# SmartWatch_SCH.net
KiCad netlist of a schematic drawn in EAGLE
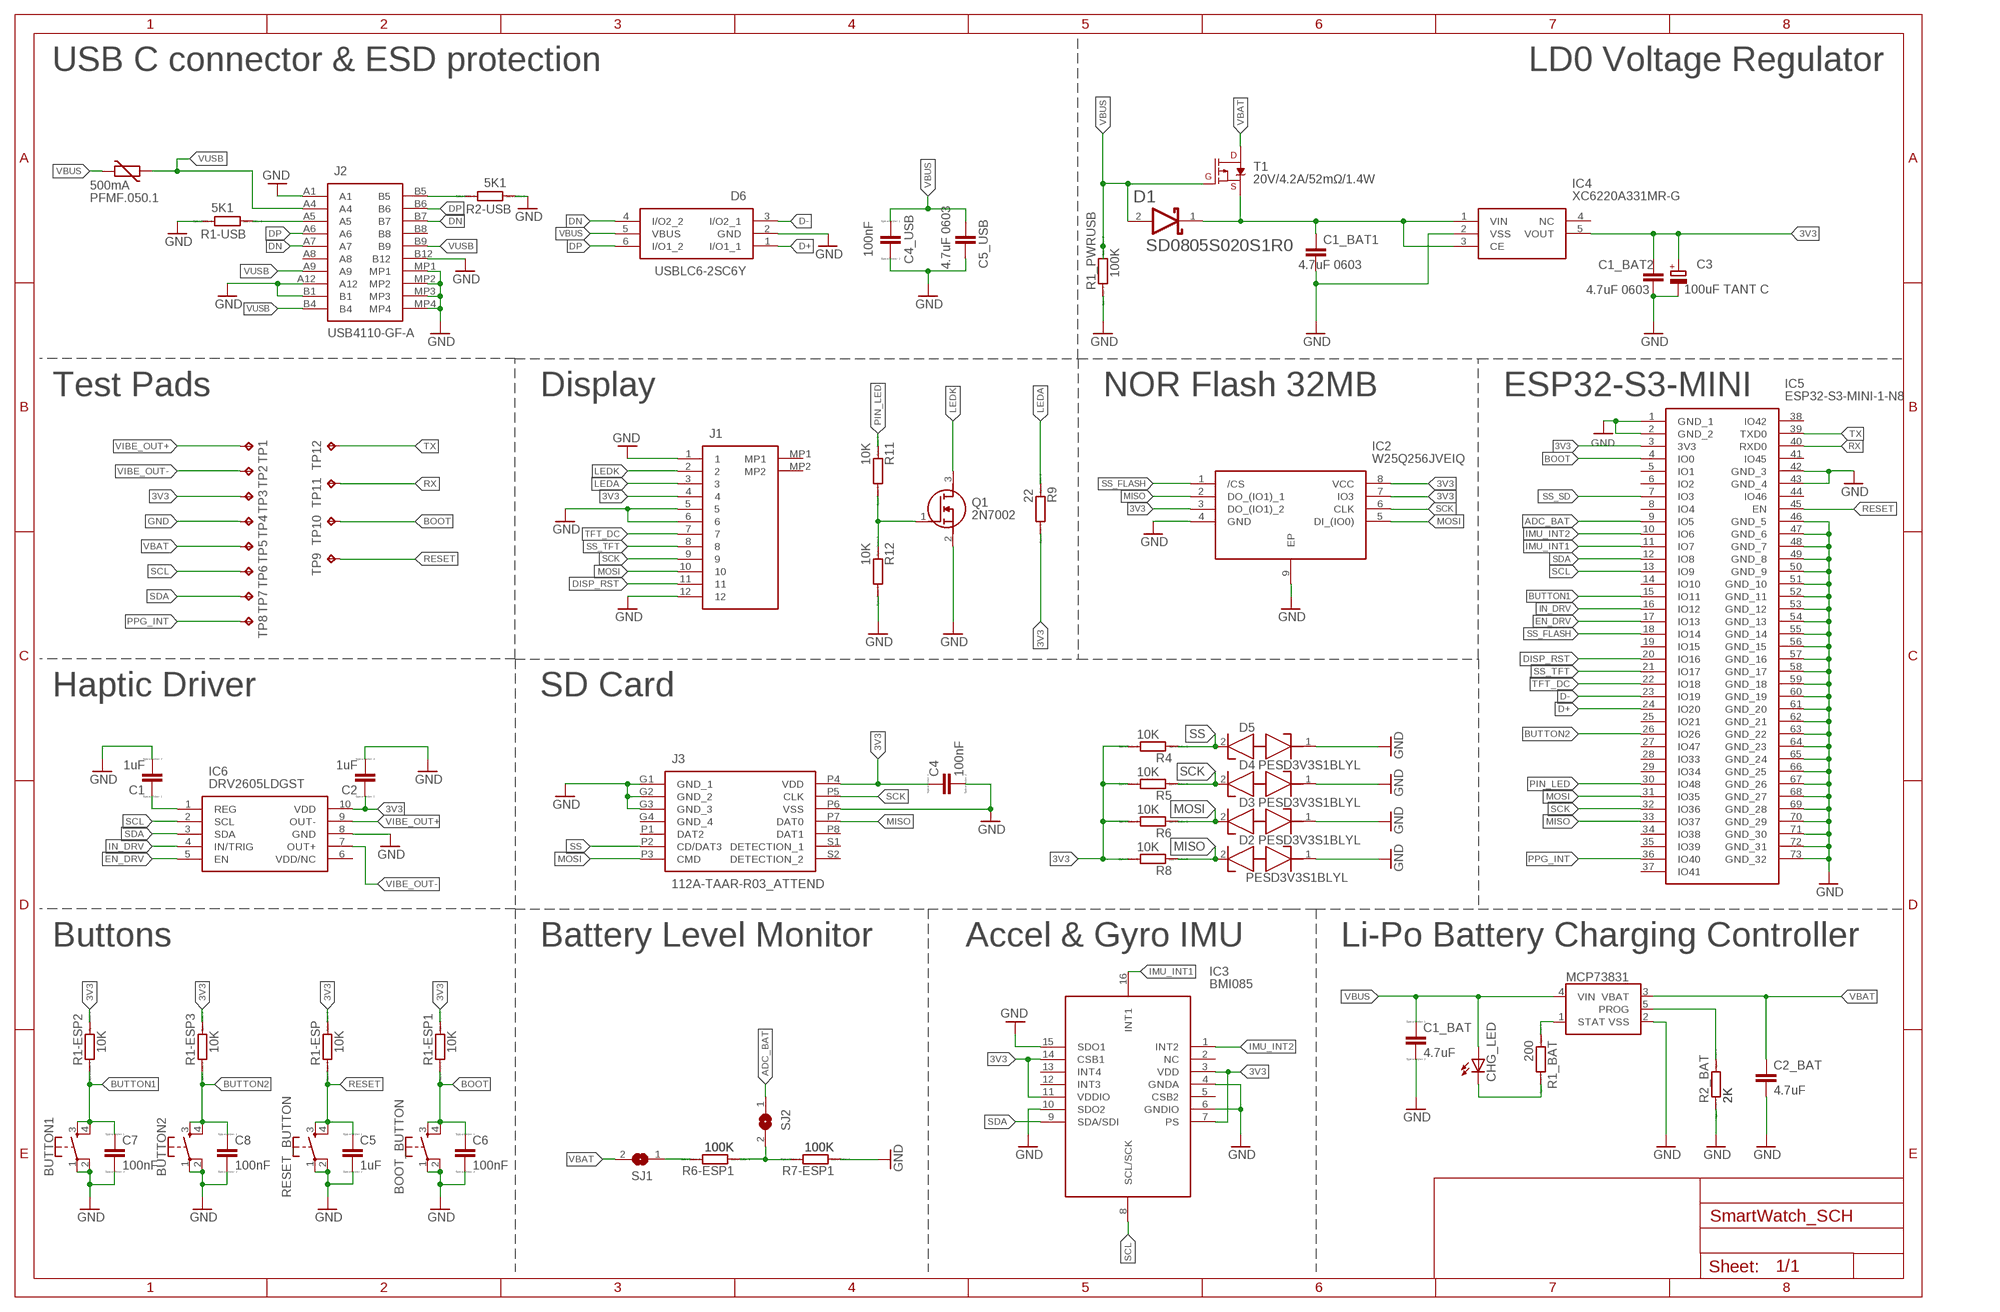
[diagram p0: schematic, sheet 1]

(export (version "E")
  (design (tool "Eeschema 10.0.6"))
  (components
    (comp (ref "BOOT_BUTTON")
      (value "SPARKFUN-SWITCHES_MOMENTARY-SWITCH-SPST-2-SMD-4.6X2.8MM")
      (footprint "eagle-import:SPARKFUN-SWITCHES_TACTILE_SWITCH_SMD_4.6X2.8MM")
      (libsource (lib "eagle-import") (part "SPARKFUN-SWITCHES_MOMENTARY-SWITCH-SPST-2-SMD-4.6X2.8MM"))
    )
    (comp (ref "BUTTON1")
      (value "SPARKFUN-SWITCHES_MOMENTARY-SWITCH-SPST-2-SMD-4.6X2.8MM")
      (footprint "eagle-import:SPARKFUN-SWITCHES_TACTILE_SWITCH_SMD_4.6X2.8MM")
      (libsource (lib "eagle-import") (part "SPARKFUN-SWITCHES_MOMENTARY-SWITCH-SPST-2-SMD-4.6X2.8MM"))
    )
    (comp (ref "BUTTON2")
      (value "SPARKFUN-SWITCHES_MOMENTARY-SWITCH-SPST-2-SMD-4.6X2.8MM")
      (footprint "eagle-import:SPARKFUN-SWITCHES_TACTILE_SWITCH_SMD_4.6X2.8MM")
      (libsource (lib "eagle-import") (part "SPARKFUN-SWITCHES_MOMENTARY-SWITCH-SPST-2-SMD-4.6X2.8MM"))
    )
    (comp (ref "C1")
      (value "1uF")
      (footprint "eagle-import:EAGLE-LTSPICE_C0402")
      (libsource (lib "eagle-import") (part "EAGLE-LTSPICE_CC0402"))
    )
    (comp (ref "C1_BAT")
      (value "4.7uF")
      (footprint "eagle-import:EAGLE-LTSPICE_C0402")
      (libsource (lib "eagle-import") (part "EAGLE-LTSPICE_CC0402"))
    )
    (comp (ref "C1_BAT1")
      (value "4.7uF 0603")
      (footprint "eagle-import:RCL_C0603")
      (libsource (lib "eagle-import") (part "RCL_C-EUC0603"))
    )
    (comp (ref "C1_BAT2")
      (value "4.7uF 0603")
      (footprint "eagle-import:RCL_C0603")
      (libsource (lib "eagle-import") (part "RCL_C-EUC0603"))
    )
    (comp (ref "C2")
      (value "1uF")
      (footprint "eagle-import:EAGLE-LTSPICE_C0402")
      (libsource (lib "eagle-import") (part "EAGLE-LTSPICE_CC0402"))
    )
    (comp (ref "C2_BAT")
      (value "4.7uF")
      (footprint "eagle-import:RCL_C0603")
      (libsource (lib "eagle-import") (part "RCL_C-EUC0603"))
    )
    (comp (ref "C3")
      (value "100uF TANT C")
      (footprint "eagle-import:CT3528")
      (libsource (lib "eagle-import") (part "CPOL-EUCT3528"))
    )
    (comp (ref "C4")
      (value "100nF")
      (footprint "eagle-import:EAGLE-LTSPICE_C0402")
      (libsource (lib "eagle-import") (part "EAGLE-LTSPICE_CC0402"))
    )
    (comp (ref "C4_USB")
      (value "100nF")
      (footprint "eagle-import:EAGLE-LTSPICE_C0402")
      (libsource (lib "eagle-import") (part "EAGLE-LTSPICE_CC0402"))
    )
    (comp (ref "C5")
      (value "1uF")
      (footprint "eagle-import:EAGLE-LTSPICE_C0402")
      (libsource (lib "eagle-import") (part "EAGLE-LTSPICE_CC0402"))
    )
    (comp (ref "C5_USB")
      (value "4.7uF 0603")
      (footprint "eagle-import:RCL_C0603")
      (libsource (lib "eagle-import") (part "RCL_C-EUC0603"))
    )
    (comp (ref "C6")
      (value "100nF")
      (footprint "eagle-import:EAGLE-LTSPICE_C0402")
      (libsource (lib "eagle-import") (part "EAGLE-LTSPICE_CC0402"))
    )
    (comp (ref "C7")
      (value "100nF")
      (footprint "eagle-import:EAGLE-LTSPICE_C0402")
      (libsource (lib "eagle-import") (part "EAGLE-LTSPICE_CC0402"))
    )
    (comp (ref "C8")
      (value "100nF")
      (footprint "eagle-import:EAGLE-LTSPICE_C0402")
      (libsource (lib "eagle-import") (part "EAGLE-LTSPICE_CC0402"))
    )
    (comp (ref "CHG_LED")
      (value "ADAFRUIT_LEDCHIP-LED0603")
      (footprint "eagle-import:ADAFRUIT_CHIP-LED0603")
      (libsource (lib "eagle-import") (part "ADAFRUIT_LEDCHIP-LED0603"))
    )
    (comp (ref "D1")
      (value "AVX---SD0805S020S1R0_AVX_SD0805S020S1R0AVX_SD0805S020S1R0_0_0")
      (footprint "eagle-import:AVX---SD0805S020S1R0_AVX_SD0805S020S1R0_0")
      (fields
        (field (name "DIGIKEY_PART_NUMBER") "478-7800-1-ND")
        (field (name "MF") "AVX")
        (field (name "MOUSER_PART_NUMBER") "581-SD0805S020S1R0")
      )
      (libsource (lib "eagle-import") (part "AVX---SD0805S020S1R0_AVX_SD0805S020S1R0AVX_SD0805S020S1R0_0_0"))
    )
    (comp (ref "D2")
      (value "PESD3V3S1BLYL")
      (footprint "eagle-import:PESD5V0S1BL315")
      (fields (field (name "MOUSER_PART_NUMBER") "771-PESD3V3S1BLYL"))
      (libsource (lib "eagle-import") (part "PESD3V3S1BLYL"))
    )
    (comp (ref "D3")
      (value "PESD3V3S1BLYL")
      (footprint "eagle-import:PESD5V0S1BL315")
      (fields (field (name "MOUSER_PART_NUMBER") "771-PESD3V3S1BLYL"))
      (libsource (lib "eagle-import") (part "PESD3V3S1BLYL"))
    )
    (comp (ref "D4")
      (value "PESD3V3S1BLYL")
      (footprint "eagle-import:PESD5V0S1BL315")
      (fields (field (name "MOUSER_PART_NUMBER") "771-PESD3V3S1BLYL"))
      (libsource (lib "eagle-import") (part "PESD3V3S1BLYL"))
    )
    (comp (ref "D5")
      (value "PESD3V3S1BLYL")
      (footprint "eagle-import:PESD5V0S1BL315")
      (fields (field (name "MOUSER_PART_NUMBER") "771-PESD3V3S1BLYL"))
      (libsource (lib "eagle-import") (part "PESD3V3S1BLYL"))
    )
    (comp (ref "D6")
      (value "USBLC6-2SC6Y")
      (footprint "eagle-import:SOT95P280X145-6N")
      (fields (field (name "MOUSER_PART_NUMBER") "511-USBLC6-2SC6Y"))
      (libsource (lib "eagle-import") (part "USBLC6-2SC6Y"))
    )
    (comp (ref "IC2")
      (value "W25Q256JVEIQ")
      (footprint "eagle-import:SON127P800X600X80-9N")
      (fields (field (name "MOUSER_PART_NUMBER") "454-W25Q256JVEIQ"))
      (libsource (lib "eagle-import") (part "W25Q256JVEIQ"))
    )
    (comp (ref "IC3")
      (value "BMI085")
      (footprint "eagle-import:BMI085")
      (fields (field (name "MOUSER_PART_NUMBER") "262-BMI085"))
      (libsource (lib "eagle-import") (part "BMI085"))
    )
    (comp (ref "IC4")
      (value "XC6220A331MR-G")
      (footprint "eagle-import:SOT95P280X120-5N")
      (fields (field (name "MOUSER_PART_NUMBER") "865-XC6220A331MR-G"))
      (libsource (lib "eagle-import") (part "XC6220A331MR-G"))
    )
    (comp (ref "IC5")
      (value "ESP32-S3-MINI-1-N8")
      (footprint "eagle-import:ESP32S3MINI1N8")
      (fields (field (name "MOUSER_PART_NUMBER") "356-ESP32-S3-MINI1N8"))
      (libsource (lib "eagle-import") (part "ESP32-S3-MINI-1-N8"))
    )
    (comp (ref "IC6")
      (value "DRV2605LDGST")
      (footprint "eagle-import:SOP50P490X110-10N")
      (fields (field (name "MOUSER_PART_NUMBER") "595-DRV2605LDGST"))
      (libsource (lib "eagle-import") (part "DRV2605LDGST"))
    )
    (comp (ref "J1")
      (value "PCA-6-LA-12-HL-3-T_R")
      (footprint "eagle-import:PCA6LA12HL3TR")
      (fields (field (name "MANUFACTURER_PART_NUMBER") "PCA-6-LA-12-HL-3-T/R"))
      (libsource (lib "eagle-import") (part "PCA-6-LA-12-HL-3-T_R"))
    )
    (comp (ref "J2")
      (value "USB4110-GF-A")
      (footprint "eagle-import:USB4110GFA")
      (fields
        (field (name "MANUFACTURER_PART_NUMBER") "USB4110-GF-A")
        (field (name "MOUSER_PART_NUMBER") "640-USB4110-GF-A")
      )
      (libsource (lib "eagle-import") (part "USB4110-GF-A"))
    )
    (comp (ref "J3")
      (value "112A-TAAR-R03_ATTEND")
      (footprint "eagle-import:112ATAARR03ATTEND")
      (fields (field (name "MANUFACTURER_PART_NUMBER") "112A-TAAR-R03 ATTEND"))
      (libsource (lib "eagle-import") (part "112A-TAAR-R03_ATTEND"))
    )
    (comp (ref "MCP73831")
      (value "SPARKFUN-IC-POWER_MCP73831")
      (footprint "eagle-import:SPARKFUN-IC-POWER_SOT23-5")
      (libsource (lib "eagle-import") (part "SPARKFUN-IC-POWER_MCP73831"))
    )
    (comp (ref "PFMF.050.1")
      (value "500mA")
      (footprint "eagle-import:VARISTOR_CT_CN1812")
      (libsource (lib "eagle-import") (part "VARISTOR_VARISTORCN1812"))
    )
    (comp (ref "Q1")
      (value "2N7002")
      (footprint "eagle-import:SOT96P240X120-3N")
      (fields (field (name "MOUSER_PART_NUMBER") "512-2N7002"))
      (libsource (lib "eagle-import") (part "2N7002"))
    )
    (comp (ref "R1-ESP")
      (value "10K")
      (footprint "eagle-import:EAGLE-LTSPICE_R0402")
      (libsource (lib "eagle-import") (part "EAGLE-LTSPICE_RR0402"))
    )
    (comp (ref "R1-ESP1")
      (value "10K")
      (footprint "eagle-import:EAGLE-LTSPICE_R0402")
      (libsource (lib "eagle-import") (part "EAGLE-LTSPICE_RR0402"))
    )
    (comp (ref "R1-ESP2")
      (value "10K")
      (footprint "eagle-import:EAGLE-LTSPICE_R0402")
      (libsource (lib "eagle-import") (part "EAGLE-LTSPICE_RR0402"))
    )
    (comp (ref "R1-ESP3")
      (value "10K")
      (footprint "eagle-import:EAGLE-LTSPICE_R0402")
      (libsource (lib "eagle-import") (part "EAGLE-LTSPICE_RR0402"))
    )
    (comp (ref "R1-USB")
      (value "5K1")
      (footprint "eagle-import:EAGLE-LTSPICE_R0402")
      (libsource (lib "eagle-import") (part "EAGLE-LTSPICE_RR0402"))
    )
    (comp (ref "R1_BAT")
      (value "200")
      (footprint "eagle-import:EAGLE-LTSPICE_R0402")
      (libsource (lib "eagle-import") (part "EAGLE-LTSPICE_RR0402"))
    )
    (comp (ref "R1_PWRUSB")
      (value "100K")
      (footprint "eagle-import:EAGLE-LTSPICE_R0402")
      (libsource (lib "eagle-import") (part "EAGLE-LTSPICE_RR0402"))
    )
    (comp (ref "R2-USB")
      (value "5K1")
      (footprint "eagle-import:EAGLE-LTSPICE_R0402")
      (libsource (lib "eagle-import") (part "EAGLE-LTSPICE_RR0402"))
    )
    (comp (ref "R2_BAT")
      (value "2K")
      (footprint "eagle-import:EAGLE-LTSPICE_R0402")
      (libsource (lib "eagle-import") (part "EAGLE-LTSPICE_RR0402"))
    )
    (comp (ref "R4")
      (value "10K")
      (footprint "eagle-import:EAGLE-LTSPICE_R0402")
      (libsource (lib "eagle-import") (part "EAGLE-LTSPICE_RR0402"))
    )
    (comp (ref "R5")
      (value "10K")
      (footprint "eagle-import:EAGLE-LTSPICE_R0402")
      (libsource (lib "eagle-import") (part "EAGLE-LTSPICE_RR0402"))
    )
    (comp (ref "R6")
      (value "10K")
      (footprint "eagle-import:EAGLE-LTSPICE_R0402")
      (libsource (lib "eagle-import") (part "EAGLE-LTSPICE_RR0402"))
    )
    (comp (ref "R6-ESP1")
      (value "100K")
      (footprint "eagle-import:EAGLE-LTSPICE_R0402")
      (libsource (lib "eagle-import") (part "EAGLE-LTSPICE_RR0402"))
    )
    (comp (ref "R7-ESP1")
      (value "100K")
      (footprint "eagle-import:EAGLE-LTSPICE_R0402")
      (libsource (lib "eagle-import") (part "EAGLE-LTSPICE_RR0402"))
    )
    (comp (ref "R8")
      (value "10K")
      (footprint "eagle-import:EAGLE-LTSPICE_R0402")
      (libsource (lib "eagle-import") (part "EAGLE-LTSPICE_RR0402"))
    )
    (comp (ref "R9")
      (value "22")
      (footprint "eagle-import:EAGLE-LTSPICE_R0402")
      (libsource (lib "eagle-import") (part "EAGLE-LTSPICE_RR0402"))
    )
    (comp (ref "R11")
      (value "10K")
      (footprint "eagle-import:EAGLE-LTSPICE_R0402")
      (libsource (lib "eagle-import") (part "EAGLE-LTSPICE_RR0402"))
    )
    (comp (ref "R12")
      (value "10K")
      (footprint "eagle-import:EAGLE-LTSPICE_R0402")
      (libsource (lib "eagle-import") (part "EAGLE-LTSPICE_RR0402"))
    )
    (comp (ref "RESET_BUTTON")
      (value "SPARKFUN-SWITCHES_MOMENTARY-SWITCH-SPST-2-SMD-4.6X2.8MM")
      (footprint "eagle-import:SPARKFUN-SWITCHES_TACTILE_SWITCH_SMD_4.6X2.8MM")
      (libsource (lib "eagle-import") (part "SPARKFUN-SWITCHES_MOMENTARY-SWITCH-SPST-2-SMD-4.6X2.8MM"))
    )
    (comp (ref "SJ1") (value "SJ") (footprint "eagle-import:SJ") (libsource (lib "eagle-import") (part "SJ")))
    (comp (ref "SJ2") (value "SJ") (footprint "eagle-import:SJ") (libsource (lib "eagle-import") (part "SJ")))
    (comp (ref "T1")
      (value "20V/4.2A/52mΩ/1.4W")
      (footprint "eagle-import:SPARKFUN-DISCRETESEMI_SOT23-3")
      (libsource (lib "eagle-import") (part "SPARKFUN-DISCRETESEMI_MOSFET_PCH-DMG2305UX-7"))
    )
    (comp (ref "TP1")
      (value "TPTP20R")
      (footprint "eagle-import:TP20R")
      (libsource (lib "eagle-import") (part "TPTP20R"))
    )
    (comp (ref "TP2")
      (value "TPTP20R")
      (footprint "eagle-import:TP20R")
      (libsource (lib "eagle-import") (part "TPTP20R"))
    )
    (comp (ref "TP3")
      (value "TPTP20R")
      (footprint "eagle-import:TP20R")
      (fields (field (name "TP_SIGNAL_NAME") "3V3"))
      (libsource (lib "eagle-import") (part "TPTP20R"))
    )
    (comp (ref "TP4")
      (value "TPTP20R")
      (footprint "eagle-import:TP20R")
      (libsource (lib "eagle-import") (part "TPTP20R"))
    )
    (comp (ref "TP5")
      (value "TPTP20R")
      (footprint "eagle-import:TP20R")
      (libsource (lib "eagle-import") (part "TPTP20R"))
    )
    (comp (ref "TP6")
      (value "TPTP20R")
      (footprint "eagle-import:TP20R")
      (libsource (lib "eagle-import") (part "TPTP20R"))
    )
    (comp (ref "TP7")
      (value "TPTP20R")
      (footprint "eagle-import:TP20R")
      (fields (field (name "TP_SIGNAL_NAME") "SDA"))
      (libsource (lib "eagle-import") (part "TPTP20R"))
    )
    (comp (ref "TP8")
      (value "TPTP20R")
      (footprint "eagle-import:TP20R")
      (fields (field (name "TP_SIGNAL_NAME") "PPG_INT"))
      (libsource (lib "eagle-import") (part "TPTP20R"))
    )
    (comp (ref "TP9")
      (value "TPTP20R")
      (footprint "eagle-import:TP20R")
      (fields (field (name "TP_SIGNAL_NAME") "RESET"))
      (libsource (lib "eagle-import") (part "TPTP20R"))
    )
    (comp (ref "TP10")
      (value "TPTP20R")
      (footprint "eagle-import:TP20R")
      (libsource (lib "eagle-import") (part "TPTP20R"))
    )
    (comp (ref "TP11")
      (value "TPTP20R")
      (footprint "eagle-import:TP20R")
      (fields (field (name "TP_SIGNAL_NAME") "RX"))
      (libsource (lib "eagle-import") (part "TPTP20R"))
    )
    (comp (ref "TP12")
      (value "TPTP20R")
      (footprint "eagle-import:TP20R")
      (fields (field (name "TP_SIGNAL_NAME") "TX"))
      (libsource (lib "eagle-import") (part "TPTP20R"))
    )
  )
  (nets
    (net (code "1") (name "3V3") (class "Default")
      (node (ref "C1_BAT2") (pin "1") (pinfunction "1_1") (pintype "passive"))
      (node (ref "C2") (pin "1") (pinfunction "1_1") (pintype "passive"))
      (node (ref "C3") (pin "+") (pinfunction "+_+") (pintype "passive"))
      (node (ref "C4") (pin "1") (pinfunction "1_1") (pintype "passive"))
      (node (ref "IC2") (pin "3") (pinfunction "DO_(IO1)_2_3") (pintype "bidirectional"))
      (node (ref "IC2") (pin "7") (pinfunction "IO3_7") (pintype "bidirectional"))
      (node (ref "IC2") (pin "8") (pinfunction "VCC_8") (pintype "bidirectional"))
      (node (ref "IC3") (pin "11") (pinfunction "VDDIO_11") (pintype "bidirectional"))
      (node (ref "IC3") (pin "14") (pinfunction "CSB1_14") (pintype "bidirectional"))
      (node (ref "IC3") (pin "3") (pinfunction "VDD_3") (pintype "bidirectional"))
      (node (ref "IC3") (pin "7") (pinfunction "PS_7") (pintype "bidirectional"))
      (node (ref "IC4") (pin "5") (pinfunction "VOUT_5") (pintype "bidirectional"))
      (node (ref "IC5") (pin "3") (pinfunction "3V3_3") (pintype "bidirectional"))
      (node (ref "IC6") (pin "10") (pinfunction "VDD_10") (pintype "bidirectional"))
      (node (ref "J1") (pin "4") (pinfunction "4_4") (pintype "bidirectional"))
      (node (ref "J3") (pin "P4") (pinfunction "VDD_P4") (pintype "bidirectional"))
      (node (ref "R1-ESP") (pin "2") (pinfunction "2_2") (pintype "passive"))
      (node (ref "R1-ESP1") (pin "2") (pinfunction "2_2") (pintype "passive"))
      (node (ref "R1-ESP2") (pin "2") (pinfunction "2_2") (pintype "passive"))
      (node (ref "R1-ESP3") (pin "2") (pinfunction "2_2") (pintype "passive"))
      (node (ref "R4") (pin "2") (pinfunction "2_2") (pintype "passive"))
      (node (ref "R5") (pin "2") (pinfunction "2_2") (pintype "passive"))
      (node (ref "R6") (pin "2") (pinfunction "2_2") (pintype "passive"))
      (node (ref "R8") (pin "2") (pinfunction "2_2") (pintype "passive"))
      (node (ref "R9") (pin "1") (pinfunction "1_1") (pintype "passive"))
      (node (ref "TP3") (pin "TP") (pinfunction "TP_TP") (pintype "input"))
    )
    (net (code "2") (name "ADC_BAT") (class "Default")
      (node (ref "IC5") (pin "9") (pinfunction "IO5_9") (pintype "bidirectional"))
      (node (ref "SJ2") (pin "1") (pinfunction "1_1") (pintype "passive"))
    )
    (net (code "3") (name "BOOT") (class "Default")
      (node (ref "BOOT_BUTTON") (pin "3") (pinfunction "3_3") (pintype "passive"))
      (node (ref "BOOT_BUTTON") (pin "4") (pinfunction "4_4") (pintype "passive"))
      (node (ref "C6") (pin "1") (pinfunction "1_1") (pintype "passive"))
      (node (ref "IC5") (pin "4") (pinfunction "IO0_4") (pintype "bidirectional"))
      (node (ref "R1-ESP1") (pin "1") (pinfunction "1_1") (pintype "passive"))
      (node (ref "TP10") (pin "TP") (pinfunction "TP_TP") (pintype "input"))
    )
    (net (code "4") (name "BUTTON1") (class "Default")
      (node (ref "BUTTON1") (pin "3") (pinfunction "3_3") (pintype "passive"))
      (node (ref "BUTTON1") (pin "4") (pinfunction "4_4") (pintype "passive"))
      (node (ref "C7") (pin "1") (pinfunction "1_1") (pintype "passive"))
      (node (ref "IC5") (pin "15") (pinfunction "IO11_15") (pintype "bidirectional"))
      (node (ref "R1-ESP2") (pin "1") (pinfunction "1_1") (pintype "passive"))
    )
    (net (code "5") (name "BUTTON2") (class "Default")
      (node (ref "BUTTON2") (pin "3") (pinfunction "3_3") (pintype "passive"))
      (node (ref "BUTTON2") (pin "4") (pinfunction "4_4") (pintype "passive"))
      (node (ref "C8") (pin "1") (pinfunction "1_1") (pintype "passive"))
      (node (ref "IC5") (pin "26") (pinfunction "IO26_26") (pintype "bidirectional"))
      (node (ref "R1-ESP3") (pin "1") (pinfunction "1_1") (pintype "passive"))
    )
    (net (code "6") (name "D+") (class "Default")
      (node (ref "D6") (pin "1") (pinfunction "I/O1_1_1") (pintype "bidirectional"))
      (node (ref "IC5") (pin "24") (pinfunction "IO20_24") (pintype "bidirectional"))
    )
    (net (code "7") (name "D-") (class "Default")
      (node (ref "D6") (pin "3") (pinfunction "I/O2_1_3") (pintype "bidirectional"))
      (node (ref "IC5") (pin "23") (pinfunction "IO19_23") (pintype "bidirectional"))
    )
    (net (code "8") (name "DISP_RST") (class "Default")
      (node (ref "IC5") (pin "20") (pinfunction "IO16_20") (pintype "bidirectional"))
      (node (ref "J1") (pin "11") (pinfunction "11_11") (pintype "bidirectional"))
    )
    (net (code "9") (name "DN") (class "Default")
      (node (ref "D6") (pin "4") (pinfunction "I/O2_2_4") (pintype "bidirectional"))
      (node (ref "J2") (pin "A7") (pinfunction "A7_A7") (pintype "bidirectional"))
      (node (ref "J2") (pin "B7") (pinfunction "B7_B7") (pintype "bidirectional"))
    )
    (net (code "10") (name "DP") (class "Default")
      (node (ref "D6") (pin "6") (pinfunction "I/O1_2_6") (pintype "bidirectional"))
      (node (ref "J2") (pin "A6") (pinfunction "A6_A6") (pintype "bidirectional"))
      (node (ref "J2") (pin "B6") (pinfunction "B6_B6") (pintype "bidirectional"))
    )
    (net (code "11") (name "EN_DRV") (class "Default")
      (node (ref "IC5") (pin "17") (pinfunction "IO13_17") (pintype "bidirectional"))
      (node (ref "IC6") (pin "5") (pinfunction "EN_5") (pintype "bidirectional"))
    )
    (net (code "12") (name "GND") (class "Default")
      (node (ref "BOOT_BUTTON") (pin "1") (pinfunction "1_1") (pintype "passive"))
      (node (ref "BOOT_BUTTON") (pin "2") (pinfunction "2_2") (pintype "passive"))
      (node (ref "BUTTON1") (pin "1") (pinfunction "1_1") (pintype "passive"))
      (node (ref "BUTTON1") (pin "2") (pinfunction "2_2") (pintype "passive"))
      (node (ref "BUTTON2") (pin "1") (pinfunction "1_1") (pintype "passive"))
      (node (ref "BUTTON2") (pin "2") (pinfunction "2_2") (pintype "passive"))
      (node (ref "C1") (pin "2") (pinfunction "2_2") (pintype "passive"))
      (node (ref "C1_BAT") (pin "2") (pinfunction "2_2") (pintype "passive"))
      (node (ref "C1_BAT1") (pin "2") (pinfunction "2_2") (pintype "passive"))
      (node (ref "C1_BAT2") (pin "2") (pinfunction "2_2") (pintype "passive"))
      (node (ref "C2") (pin "2") (pinfunction "2_2") (pintype "passive"))
      (node (ref "C2_BAT") (pin "2") (pinfunction "2_2") (pintype "passive"))
      (node (ref "C3") (pin "-") (pinfunction "-_-") (pintype "passive"))
      (node (ref "C4") (pin "2") (pinfunction "2_2") (pintype "passive"))
      (node (ref "C4_USB") (pin "2") (pinfunction "2_2") (pintype "passive"))
      (node (ref "C5") (pin "2") (pinfunction "2_2") (pintype "passive"))
      (node (ref "C5_USB") (pin "2") (pinfunction "2_2") (pintype "passive"))
      (node (ref "C6") (pin "2") (pinfunction "2_2") (pintype "passive"))
      (node (ref "C7") (pin "2") (pinfunction "2_2") (pintype "passive"))
      (node (ref "C8") (pin "2") (pinfunction "2_2") (pintype "passive"))
      (node (ref "D2") (pin "1") (pinfunction "K1_1") (pintype "bidirectional"))
      (node (ref "D3") (pin "1") (pinfunction "K1_1") (pintype "bidirectional"))
      (node (ref "D4") (pin "1") (pinfunction "K1_1") (pintype "bidirectional"))
      (node (ref "D5") (pin "1") (pinfunction "K1_1") (pintype "bidirectional"))
      (node (ref "D6") (pin "2") (pinfunction "GND_2") (pintype "bidirectional"))
      (node (ref "IC2") (pin "4") (pinfunction "GND_4") (pintype "bidirectional"))
      (node (ref "IC2") (pin "9") (pinfunction "EP_9") (pintype "bidirectional"))
      (node (ref "IC3") (pin "10") (pinfunction "SDO2_10") (pintype "bidirectional"))
      (node (ref "IC3") (pin "15") (pinfunction "SDO1_15") (pintype "bidirectional"))
      (node (ref "IC3") (pin "4") (pinfunction "GNDA_4") (pintype "bidirectional"))
      (node (ref "IC3") (pin "6") (pinfunction "GNDIO_6") (pintype "bidirectional"))
      (node (ref "IC4") (pin "2") (pinfunction "VSS_2") (pintype "bidirectional"))
      (node (ref "IC5") (pin "1") (pinfunction "GND_1_1") (pintype "bidirectional"))
      (node (ref "IC5") (pin "2") (pinfunction "GND_2_2") (pintype "bidirectional"))
      (node (ref "IC5") (pin "42") (pinfunction "GND_3_42") (pintype "bidirectional"))
      (node (ref "IC5") (pin "43") (pinfunction "GND_4_43") (pintype "bidirectional"))
      (node (ref "IC5") (pin "46") (pinfunction "GND_5_46") (pintype "bidirectional"))
      (node (ref "IC5") (pin "47") (pinfunction "GND_6_47") (pintype "bidirectional"))
      (node (ref "IC5") (pin "48") (pinfunction "GND_7_48") (pintype "bidirectional"))
      (node (ref "IC5") (pin "49") (pinfunction "GND_8_49") (pintype "bidirectional"))
      (node (ref "IC5") (pin "50") (pinfunction "GND_9_50") (pintype "bidirectional"))
      (node (ref "IC5") (pin "51") (pinfunction "GND_10_51") (pintype "bidirectional"))
      (node (ref "IC5") (pin "52") (pinfunction "GND_11_52") (pintype "bidirectional"))
      (node (ref "IC5") (pin "53") (pinfunction "GND_12_53") (pintype "bidirectional"))
      (node (ref "IC5") (pin "54") (pinfunction "GND_13_54") (pintype "bidirectional"))
      (node (ref "IC5") (pin "55") (pinfunction "GND_14_55") (pintype "bidirectional"))
      (node (ref "IC5") (pin "56") (pinfunction "GND_15_56") (pintype "bidirectional"))
      (node (ref "IC5") (pin "57") (pinfunction "GND_16_57") (pintype "bidirectional"))
      (node (ref "IC5") (pin "58") (pinfunction "GND_17_58") (pintype "bidirectional"))
      (node (ref "IC5") (pin "59") (pinfunction "GND_18_59") (pintype "bidirectional"))
      (node (ref "IC5") (pin "60") (pinfunction "GND_19_60") (pintype "bidirectional"))
      (node (ref "IC5") (pin "61") (pinfunction "GND_20_61") (pintype "bidirectional"))
      (node (ref "IC5") (pin "62") (pinfunction "GND_21_62") (pintype "bidirectional"))
      (node (ref "IC5") (pin "63") (pinfunction "GND_22_63") (pintype "bidirectional"))
      (node (ref "IC5") (pin "64") (pinfunction "GND_23_64") (pintype "bidirectional"))
      (node (ref "IC5") (pin "65") (pinfunction "GND_24_65") (pintype "bidirectional"))
      (node (ref "IC5") (pin "66") (pinfunction "GND_25_66") (pintype "bidirectional"))
      (node (ref "IC5") (pin "67") (pinfunction "GND_26_67") (pintype "bidirectional"))
      (node (ref "IC5") (pin "68") (pinfunction "GND_27_68") (pintype "bidirectional"))
      (node (ref "IC5") (pin "69") (pinfunction "GND_28_69") (pintype "bidirectional"))
      (node (ref "IC5") (pin "70") (pinfunction "GND_29_70") (pintype "bidirectional"))
      (node (ref "IC5") (pin "71") (pinfunction "GND_30_71") (pintype "bidirectional"))
      (node (ref "IC5") (pin "72") (pinfunction "GND_31_72") (pintype "bidirectional"))
      (node (ref "IC5") (pin "73") (pinfunction "GND_32_73") (pintype "bidirectional"))
      (node (ref "IC6") (pin "8") (pinfunction "GND_8") (pintype "bidirectional"))
      (node (ref "J1") (pin "1") (pinfunction "1_1") (pintype "bidirectional"))
      (node (ref "J1") (pin "12") (pinfunction "12_12") (pintype "bidirectional"))
      (node (ref "J1") (pin "5") (pinfunction "5_5") (pintype "bidirectional"))
      (node (ref "J1") (pin "6") (pinfunction "6_6") (pintype "bidirectional"))
      (node (ref "J2") (pin "A1") (pinfunction "A1_A1") (pintype "bidirectional"))
      (node (ref "J2") (pin "A12") (pinfunction "A12_A12") (pintype "bidirectional"))
      (node (ref "J2") (pin "B1") (pinfunction "B1_B1") (pintype "bidirectional"))
      (node (ref "J2") (pin "B12") (pinfunction "B12_B12") (pintype "bidirectional"))
      (node (ref "J2") (pin "MP1") (pinfunction "MP1_MP1") (pintype "bidirectional"))
      (node (ref "J2") (pin "MP2") (pinfunction "MP2_MP2") (pintype "bidirectional"))
      (node (ref "J2") (pin "MP3") (pinfunction "MP3_MP3") (pintype "bidirectional"))
      (node (ref "J2") (pin "MP4") (pinfunction "MP4_MP4") (pintype "bidirectional"))
      (node (ref "J3") (pin "G1") (pinfunction "GND_1_G1") (pintype "bidirectional"))
      (node (ref "J3") (pin "G2") (pinfunction "GND_2_G2") (pintype "bidirectional"))
      (node (ref "J3") (pin "G3") (pinfunction "GND_3_G3") (pintype "bidirectional"))
      (node (ref "J3") (pin "P6") (pinfunction "VSS_P6") (pintype "bidirectional"))
      (node (ref "MCP73831") (pin "2") (pinfunction "VSS_2") (pintype "power_in"))
      (node (ref "Q1") (pin "2") (pinfunction "S_2") (pintype "bidirectional"))
      (node (ref "R1-USB") (pin "2") (pinfunction "2_2") (pintype "passive"))
      (node (ref "R12") (pin "1") (pinfunction "1_1") (pintype "passive"))
      (node (ref "R1_PWRUSB") (pin "1") (pinfunction "1_1") (pintype "passive"))
      (node (ref "R2-USB") (pin "1") (pinfunction "1_1") (pintype "passive"))
      (node (ref "R2_BAT") (pin "1") (pinfunction "1_1") (pintype "passive"))
      (node (ref "R7-ESP1") (pin "1") (pinfunction "1_1") (pintype "passive"))
      (node (ref "RESET_BUTTON") (pin "1") (pinfunction "1_1") (pintype "passive"))
      (node (ref "RESET_BUTTON") (pin "2") (pinfunction "2_2") (pintype "passive"))
      (node (ref "TP4") (pin "TP") (pinfunction "TP_TP") (pintype "input"))
    )
    (net (code "13") (name "IMU_INT1") (class "Default")
      (node (ref "IC3") (pin "16") (pinfunction "INT1_16") (pintype "bidirectional"))
      (node (ref "IC5") (pin "11") (pinfunction "IO7_11") (pintype "bidirectional"))
    )
    (net (code "14") (name "IMU_INT2") (class "Default")
      (node (ref "IC3") (pin "1") (pinfunction "INT2_1") (pintype "bidirectional"))
      (node (ref "IC5") (pin "10") (pinfunction "IO6_10") (pintype "bidirectional"))
    )
    (net (code "15") (name "IN_DRV") (class "Default")
      (node (ref "IC5") (pin "16") (pinfunction "IO12_16") (pintype "bidirectional"))
      (node (ref "IC6") (pin "4") (pinfunction "IN/TRIG_4") (pintype "bidirectional"))
    )
    (net (code "16") (name "LEDA") (class "Default")
      (node (ref "J1") (pin "3") (pinfunction "3_3") (pintype "bidirectional"))
      (node (ref "R9") (pin "2") (pinfunction "2_2") (pintype "passive"))
    )
    (net (code "17") (name "LEDK") (class "Default")
      (node (ref "J1") (pin "2") (pinfunction "2_2") (pintype "bidirectional"))
      (node (ref "Q1") (pin "3") (pinfunction "D_3") (pintype "bidirectional"))
    )
    (net (code "18") (name "MISO") (class "Default")
      (node (ref "D2") (pin "2") (pinfunction "K2_2") (pintype "bidirectional"))
      (node (ref "IC2") (pin "2") (pinfunction "DO_(IO1)_1_2") (pintype "bidirectional"))
      (node (ref "IC5") (pin "33") (pinfunction "IO37_33") (pintype "bidirectional"))
      (node (ref "J3") (pin "P7") (pinfunction "DAT0_P7") (pintype "bidirectional"))
      (node (ref "R8") (pin "1") (pinfunction "1_1") (pintype "passive"))
    )
    (net (code "19") (name "MOSI") (class "Default")
      (node (ref "D3") (pin "2") (pinfunction "K2_2") (pintype "bidirectional"))
      (node (ref "IC2") (pin "5") (pinfunction "DI_(IO0)_5") (pintype "bidirectional"))
      (node (ref "IC5") (pin "31") (pinfunction "IO35_31") (pintype "bidirectional"))
      (node (ref "J1") (pin "10") (pinfunction "10_10") (pintype "bidirectional"))
      (node (ref "J3") (pin "P3") (pinfunction "CMD_P3") (pintype "bidirectional"))
      (node (ref "R6") (pin "1") (pinfunction "1_1") (pintype "passive"))
    )
    (net (code "20") (name "Net-(CHG_LED-PadC)") (class "Default")
      (node (ref "CHG_LED") (pin "C") (pinfunction "C_C") (pintype "passive"))
      (node (ref "R1_BAT") (pin "2") (pinfunction "2_2") (pintype "passive"))
    )
    (net (code "21") (name "Net-(D1-CATHODE)") (class "Default")
      (node (ref "C1_BAT1") (pin "1") (pinfunction "1_1") (pintype "passive"))
      (node (ref "D1") (pin "1") (pinfunction "CATHODE_1") (pintype "bidirectional"))
      (node (ref "IC4") (pin "1") (pinfunction "VIN_1") (pintype "bidirectional"))
      (node (ref "IC4") (pin "3") (pinfunction "CE_3") (pintype "bidirectional"))
      (node (ref "T1") (pin "2") (pinfunction "S_2") (pintype "bidirectional"))
    )
    (net (code "22") (name "Net-(IC6-REG)") (class "Default")
      (node (ref "C1") (pin "1") (pinfunction "1_1") (pintype "passive"))
      (node (ref "IC6") (pin "1") (pinfunction "REG_1") (pintype "bidirectional"))
    )
    (net (code "23") (name "Net-(J2-PadA5)") (class "Default")
      (node (ref "J2") (pin "A5") (pinfunction "A5_A5") (pintype "bidirectional"))
      (node (ref "R1-USB") (pin "1") (pinfunction "1_1") (pintype "passive"))
    )
    (net (code "24") (name "Net-(J2-PadB5)") (class "Default")
      (node (ref "J2") (pin "B5") (pinfunction "B5_B5") (pintype "bidirectional"))
      (node (ref "R2-USB") (pin "2") (pinfunction "2_2") (pintype "passive"))
    )
    (net (code "25") (name "Net-(MCP73831-PROG)") (class "Default")
      (node (ref "MCP73831") (pin "5") (pinfunction "PROG_5") (pintype "input"))
      (node (ref "R2_BAT") (pin "2") (pinfunction "2_2") (pintype "passive"))
    )
    (net (code "26") (name "Net-(MCP73831-STAT)") (class "Default")
      (node (ref "MCP73831") (pin "1") (pinfunction "STAT_1") (pintype "output"))
      (node (ref "R1_BAT") (pin "1") (pinfunction "1_1") (pintype "passive"))
    )
    (net (code "27") (name "Net-(Q1-G)") (class "Default")
      (node (ref "Q1") (pin "1") (pinfunction "G_1") (pintype "bidirectional"))
      (node (ref "R11") (pin "1") (pinfunction "1_1") (pintype "passive"))
      (node (ref "R12") (pin "2") (pinfunction "2_2") (pintype "passive"))
    )
    (net (code "28") (name "Net-(R6-ESP1-Pad1)") (class "Default")
      (node (ref "R6-ESP1") (pin "1") (pinfunction "1_1") (pintype "passive"))
      (node (ref "R7-ESP1") (pin "2") (pinfunction "2_2") (pintype "passive"))
      (node (ref "SJ2") (pin "2") (pinfunction "2_2") (pintype "passive"))
    )
    (net (code "29") (name "Net-(R6-ESP1-Pad2)") (class "Default")
      (node (ref "R6-ESP1") (pin "2") (pinfunction "2_2") (pintype "passive"))
      (node (ref "SJ1") (pin "1") (pinfunction "1_1") (pintype "passive"))
    )
    (net (code "30") (name "PIN_LED") (class "Default")
      (node (ref "IC5") (pin "30") (pinfunction "IO48_30") (pintype "bidirectional"))
      (node (ref "R11") (pin "2") (pinfunction "2_2") (pintype "passive"))
    )
    (net (code "31") (name "PPG_INT") (class "Default")
      (node (ref "IC5") (pin "36") (pinfunction "IO40_36") (pintype "bidirectional"))
      (node (ref "TP8") (pin "TP") (pinfunction "TP_TP") (pintype "input"))
    )
    (net (code "32") (name "RESET") (class "Default")
      (node (ref "C5") (pin "1") (pinfunction "1_1") (pintype "passive"))
      (node (ref "IC5") (pin "45") (pinfunction "EN_45") (pintype "bidirectional"))
      (node (ref "R1-ESP") (pin "1") (pinfunction "1_1") (pintype "passive"))
      (node (ref "RESET_BUTTON") (pin "3") (pinfunction "3_3") (pintype "passive"))
      (node (ref "RESET_BUTTON") (pin "4") (pinfunction "4_4") (pintype "passive"))
      (node (ref "TP9") (pin "TP") (pinfunction "TP_TP") (pintype "input"))
    )
    (net (code "33") (name "RX") (class "Default")
      (node (ref "IC5") (pin "40") (pinfunction "RXD0_40") (pintype "bidirectional"))
      (node (ref "TP11") (pin "TP") (pinfunction "TP_TP") (pintype "input"))
    )
    (net (code "34") (name "SCK") (class "Default")
      (node (ref "D4") (pin "2") (pinfunction "K2_2") (pintype "bidirectional"))
      (node (ref "IC2") (pin "6") (pinfunction "CLK_6") (pintype "bidirectional"))
      (node (ref "IC5") (pin "32") (pinfunction "IO36_32") (pintype "bidirectional"))
      (node (ref "J1") (pin "9") (pinfunction "9_9") (pintype "bidirectional"))
      (node (ref "J3") (pin "P5") (pinfunction "CLK_P5") (pintype "bidirectional"))
      (node (ref "R5") (pin "1") (pinfunction "1_1") (pintype "passive"))
    )
    (net (code "35") (name "SCL") (class "Default")
      (node (ref "IC3") (pin "8") (pinfunction "SCL/SCK_8") (pintype "bidirectional"))
      (node (ref "IC5") (pin "13") (pinfunction "IO9_13") (pintype "bidirectional"))
      (node (ref "IC6") (pin "2") (pinfunction "SCL_2") (pintype "bidirectional"))
      (node (ref "TP6") (pin "TP") (pinfunction "TP_TP") (pintype "input"))
    )
    (net (code "36") (name "SDA") (class "Default")
      (node (ref "IC3") (pin "9") (pinfunction "SDA/SDI_9") (pintype "bidirectional"))
      (node (ref "IC5") (pin "12") (pinfunction "IO8_12") (pintype "bidirectional"))
      (node (ref "IC6") (pin "3") (pinfunction "SDA_3") (pintype "bidirectional"))
      (node (ref "TP7") (pin "TP") (pinfunction "TP_TP") (pintype "input"))
    )
    (net (code "37") (name "SS") (class "Default")
      (node (ref "D5") (pin "2") (pinfunction "K2_2") (pintype "bidirectional"))
      (node (ref "J3") (pin "P2") (pinfunction "CD/DAT3_P2") (pintype "bidirectional"))
      (node (ref "R4") (pin "1") (pinfunction "1_1") (pintype "passive"))
    )
    (net (code "38") (name "SS_FLASH") (class "Default")
      (node (ref "IC2") (pin "1") (pinfunction "/CS_1") (pintype "bidirectional"))
      (node (ref "IC5") (pin "18") (pinfunction "IO14_18") (pintype "bidirectional"))
    )
    (net (code "39") (name "SS_SD") (class "Default")
      (node (ref "IC5") (pin "7") (pinfunction "IO3_7") (pintype "bidirectional"))
    )
    (net (code "40") (name "SS_TFT") (class "Default")
      (node (ref "IC5") (pin "21") (pinfunction "IO17_21") (pintype "bidirectional"))
      (node (ref "J1") (pin "8") (pinfunction "8_8") (pintype "bidirectional"))
    )
    (net (code "41") (name "TFT_DC") (class "Default")
      (node (ref "IC5") (pin "22") (pinfunction "IO18_22") (pintype "bidirectional"))
      (node (ref "J1") (pin "7") (pinfunction "7_7") (pintype "bidirectional"))
    )
    (net (code "42") (name "TX") (class "Default")
      (node (ref "IC5") (pin "39") (pinfunction "TXD0_39") (pintype "bidirectional"))
      (node (ref "TP12") (pin "TP") (pinfunction "TP_TP") (pintype "input"))
    )
    (net (code "43") (name "VBAT") (class "Default")
      (node (ref "C2_BAT") (pin "1") (pinfunction "1_1") (pintype "passive"))
      (node (ref "MCP73831") (pin "3") (pinfunction "VBAT_3") (pintype "power_in"))
      (node (ref "SJ1") (pin "2") (pinfunction "2_2") (pintype "passive"))
      (node (ref "T1") (pin "3") (pinfunction "D_3") (pintype "bidirectional"))
      (node (ref "TP5") (pin "TP") (pinfunction "TP_TP") (pintype "input"))
    )
    (net (code "44") (name "VBUS") (class "Default")
      (node (ref "C1_BAT") (pin "1") (pinfunction "1_1") (pintype "passive"))
      (node (ref "C4_USB") (pin "1") (pinfunction "1_1") (pintype "passive"))
      (node (ref "C5_USB") (pin "1") (pinfunction "1_1") (pintype "passive"))
      (node (ref "CHG_LED") (pin "A") (pinfunction "A_A") (pintype "passive"))
      (node (ref "D1") (pin "2") (pinfunction "ANODE_2") (pintype "bidirectional"))
      (node (ref "D6") (pin "5") (pinfunction "VBUS_5") (pintype "bidirectional"))
      (node (ref "MCP73831") (pin "4") (pinfunction "VIN_4") (pintype "power_in"))
      (node (ref "PFMF.050.1") (pin "2") (pinfunction "2_2") (pintype "passive"))
      (node (ref "R1_PWRUSB") (pin "2") (pinfunction "2_2") (pintype "passive"))
      (node (ref "T1") (pin "1") (pinfunction "G_1") (pintype "bidirectional"))
    )
    (net (code "45") (name "VIBE_OUT+") (class "Default")
      (node (ref "IC6") (pin "9") (pinfunction "OUT-_9") (pintype "bidirectional"))
      (node (ref "TP1") (pin "TP") (pinfunction "TP_TP") (pintype "input"))
    )
    (net (code "46") (name "VIBE_OUT-") (class "Default")
      (node (ref "IC6") (pin "7") (pinfunction "OUT+_7") (pintype "bidirectional"))
      (node (ref "TP2") (pin "TP") (pinfunction "TP_TP") (pintype "input"))
    )
    (net (code "47") (name "VUSB") (class "Default")
      (node (ref "J2") (pin "A4") (pinfunction "A4_A4") (pintype "bidirectional"))
      (node (ref "J2") (pin "A9") (pinfunction "A9_A9") (pintype "bidirectional"))
      (node (ref "J2") (pin "B4") (pinfunction "B4_B4") (pintype "bidirectional"))
      (node (ref "J2") (pin "B9") (pinfunction "B9_B9") (pintype "bidirectional"))
      (node (ref "PFMF.050.1") (pin "1") (pinfunction "1_1") (pintype "passive"))
    )
    (net (code "48") (name "unconnected-(IC3-CSB2-Pad5)") (class "Default")
      (node (ref "IC3") (pin "5") (pinfunction "CSB2_5") (pintype "bidirectional"))
    )
    (net (code "49") (name "unconnected-(IC3-INT3-Pad12)") (class "Default")
      (node (ref "IC3") (pin "12") (pinfunction "INT3_12") (pintype "bidirectional"))
    )
    (net (code "50") (name "unconnected-(IC3-INT4-Pad13)") (class "Default")
      (node (ref "IC3") (pin "13") (pinfunction "INT4_13") (pintype "bidirectional"))
    )
    (net (code "51") (name "unconnected-(IC3-NC-Pad2)") (class "Default")
      (node (ref "IC3") (pin "2") (pinfunction "NC_2") (pintype "no_connect"))
    )
    (net (code "52") (name "unconnected-(IC4-NC-Pad4)") (class "Default")
      (node (ref "IC4") (pin "4") (pinfunction "NC_4") (pintype "no_connect"))
    )
    (net (code "53") (name "unconnected-(IC5-IO1-Pad5)") (class "Default")
      (node (ref "IC5") (pin "5") (pinfunction "IO1_5") (pintype "bidirectional"))
    )
    (net (code "54") (name "unconnected-(IC5-IO2-Pad6)") (class "Default")
      (node (ref "IC5") (pin "6") (pinfunction "IO2_6") (pintype "bidirectional"))
    )
    (net (code "55") (name "unconnected-(IC5-IO4-Pad8)") (class "Default")
      (node (ref "IC5") (pin "8") (pinfunction "IO4_8") (pintype "bidirectional"))
    )
    (net (code "56") (name "unconnected-(IC5-IO10-Pad14)") (class "Default")
      (node (ref "IC5") (pin "14") (pinfunction "IO10_14") (pintype "bidirectional"))
    )
    (net (code "57") (name "unconnected-(IC5-IO15-Pad19)") (class "Default")
      (node (ref "IC5") (pin "19") (pinfunction "IO15_19") (pintype "bidirectional"))
    )
    (net (code "58") (name "unconnected-(IC5-IO21-Pad25)") (class "Default")
      (node (ref "IC5") (pin "25") (pinfunction "IO21_25") (pintype "bidirectional"))
    )
    (net (code "59") (name "unconnected-(IC5-IO33-Pad28)") (class "Default")
      (node (ref "IC5") (pin "28") (pinfunction "IO33_28") (pintype "bidirectional"))
    )
    (net (code "60") (name "unconnected-(IC5-IO34-Pad29)") (class "Default")
      (node (ref "IC5") (pin "29") (pinfunction "IO34_29") (pintype "bidirectional"))
    )
    (net (code "61") (name "unconnected-(IC5-IO38-Pad34)") (class "Default")
      (node (ref "IC5") (pin "34") (pinfunction "IO38_34") (pintype "bidirectional"))
    )
    (net (code "62") (name "unconnected-(IC5-IO39-Pad35)") (class "Default")
      (node (ref "IC5") (pin "35") (pinfunction "IO39_35") (pintype "bidirectional"))
    )
    (net (code "63") (name "unconnected-(IC5-IO41-Pad37)") (class "Default")
      (node (ref "IC5") (pin "37") (pinfunction "IO41_37") (pintype "bidirectional"))
    )
    (net (code "64") (name "unconnected-(IC5-IO42-Pad38)") (class "Default")
      (node (ref "IC5") (pin "38") (pinfunction "IO42_38") (pintype "bidirectional"))
    )
    (net (code "65") (name "unconnected-(IC5-IO45-Pad41)") (class "Default")
      (node (ref "IC5") (pin "41") (pinfunction "IO45_41") (pintype "bidirectional"))
    )
    (net (code "66") (name "unconnected-(IC5-IO46-Pad44)") (class "Default")
      (node (ref "IC5") (pin "44") (pinfunction "IO46_44") (pintype "bidirectional"))
    )
    (net (code "67") (name "unconnected-(IC5-IO47-Pad27)") (class "Default")
      (node (ref "IC5") (pin "27") (pinfunction "IO47_27") (pintype "bidirectional"))
    )
    (net (code "68") (name "unconnected-(IC6-VDD{slash}NC-Pad6)") (class "Default")
      (node (ref "IC6") (pin "6") (pinfunction "VDD/NC_6") (pintype "bidirectional"))
    )
    (net (code "69") (name "unconnected-(J1-PadMP1)") (class "Default")
      (node (ref "J1") (pin "MP1") (pinfunction "MP1_MP1") (pintype "bidirectional"))
    )
    (net (code "70") (name "unconnected-(J1-PadMP2)") (class "Default")
      (node (ref "J1") (pin "MP2") (pinfunction "MP2_MP2") (pintype "bidirectional"))
    )
    (net (code "71") (name "unconnected-(J2-PadA8)") (class "Default")
      (node (ref "J2") (pin "A8") (pinfunction "A8_A8") (pintype "bidirectional"))
    )
    (net (code "72") (name "unconnected-(J2-PadB8)") (class "Default")
      (node (ref "J2") (pin "B8") (pinfunction "B8_B8") (pintype "bidirectional"))
    )
    (net (code "73") (name "unconnected-(J3-DAT1-PadP8)") (class "Default")
      (node (ref "J3") (pin "P8") (pinfunction "DAT1_P8") (pintype "bidirectional"))
    )
    (net (code "74") (name "unconnected-(J3-DAT2-PadP1)") (class "Default")
      (node (ref "J3") (pin "P1") (pinfunction "DAT2_P1") (pintype "bidirectional"))
    )
    (net (code "75") (name "unconnected-(J3-DETECTION_1-PadS1)") (class "Default")
      (node (ref "J3") (pin "S1") (pinfunction "DETECTION_1_S1") (pintype "bidirectional"))
    )
    (net (code "76") (name "unconnected-(J3-DETECTION_2-PadS2)") (class "Default")
      (node (ref "J3") (pin "S2") (pinfunction "DETECTION_2_S2") (pintype "bidirectional"))
    )
    (net (code "77") (name "unconnected-(J3-GND_4-PadG4)") (class "Default")
      (node (ref "J3") (pin "G4") (pinfunction "GND_4_G4") (pintype "bidirectional"))
    )
  )
)
